# usv_board.net
KiCad netlist of a schematic drawn in EAGLE
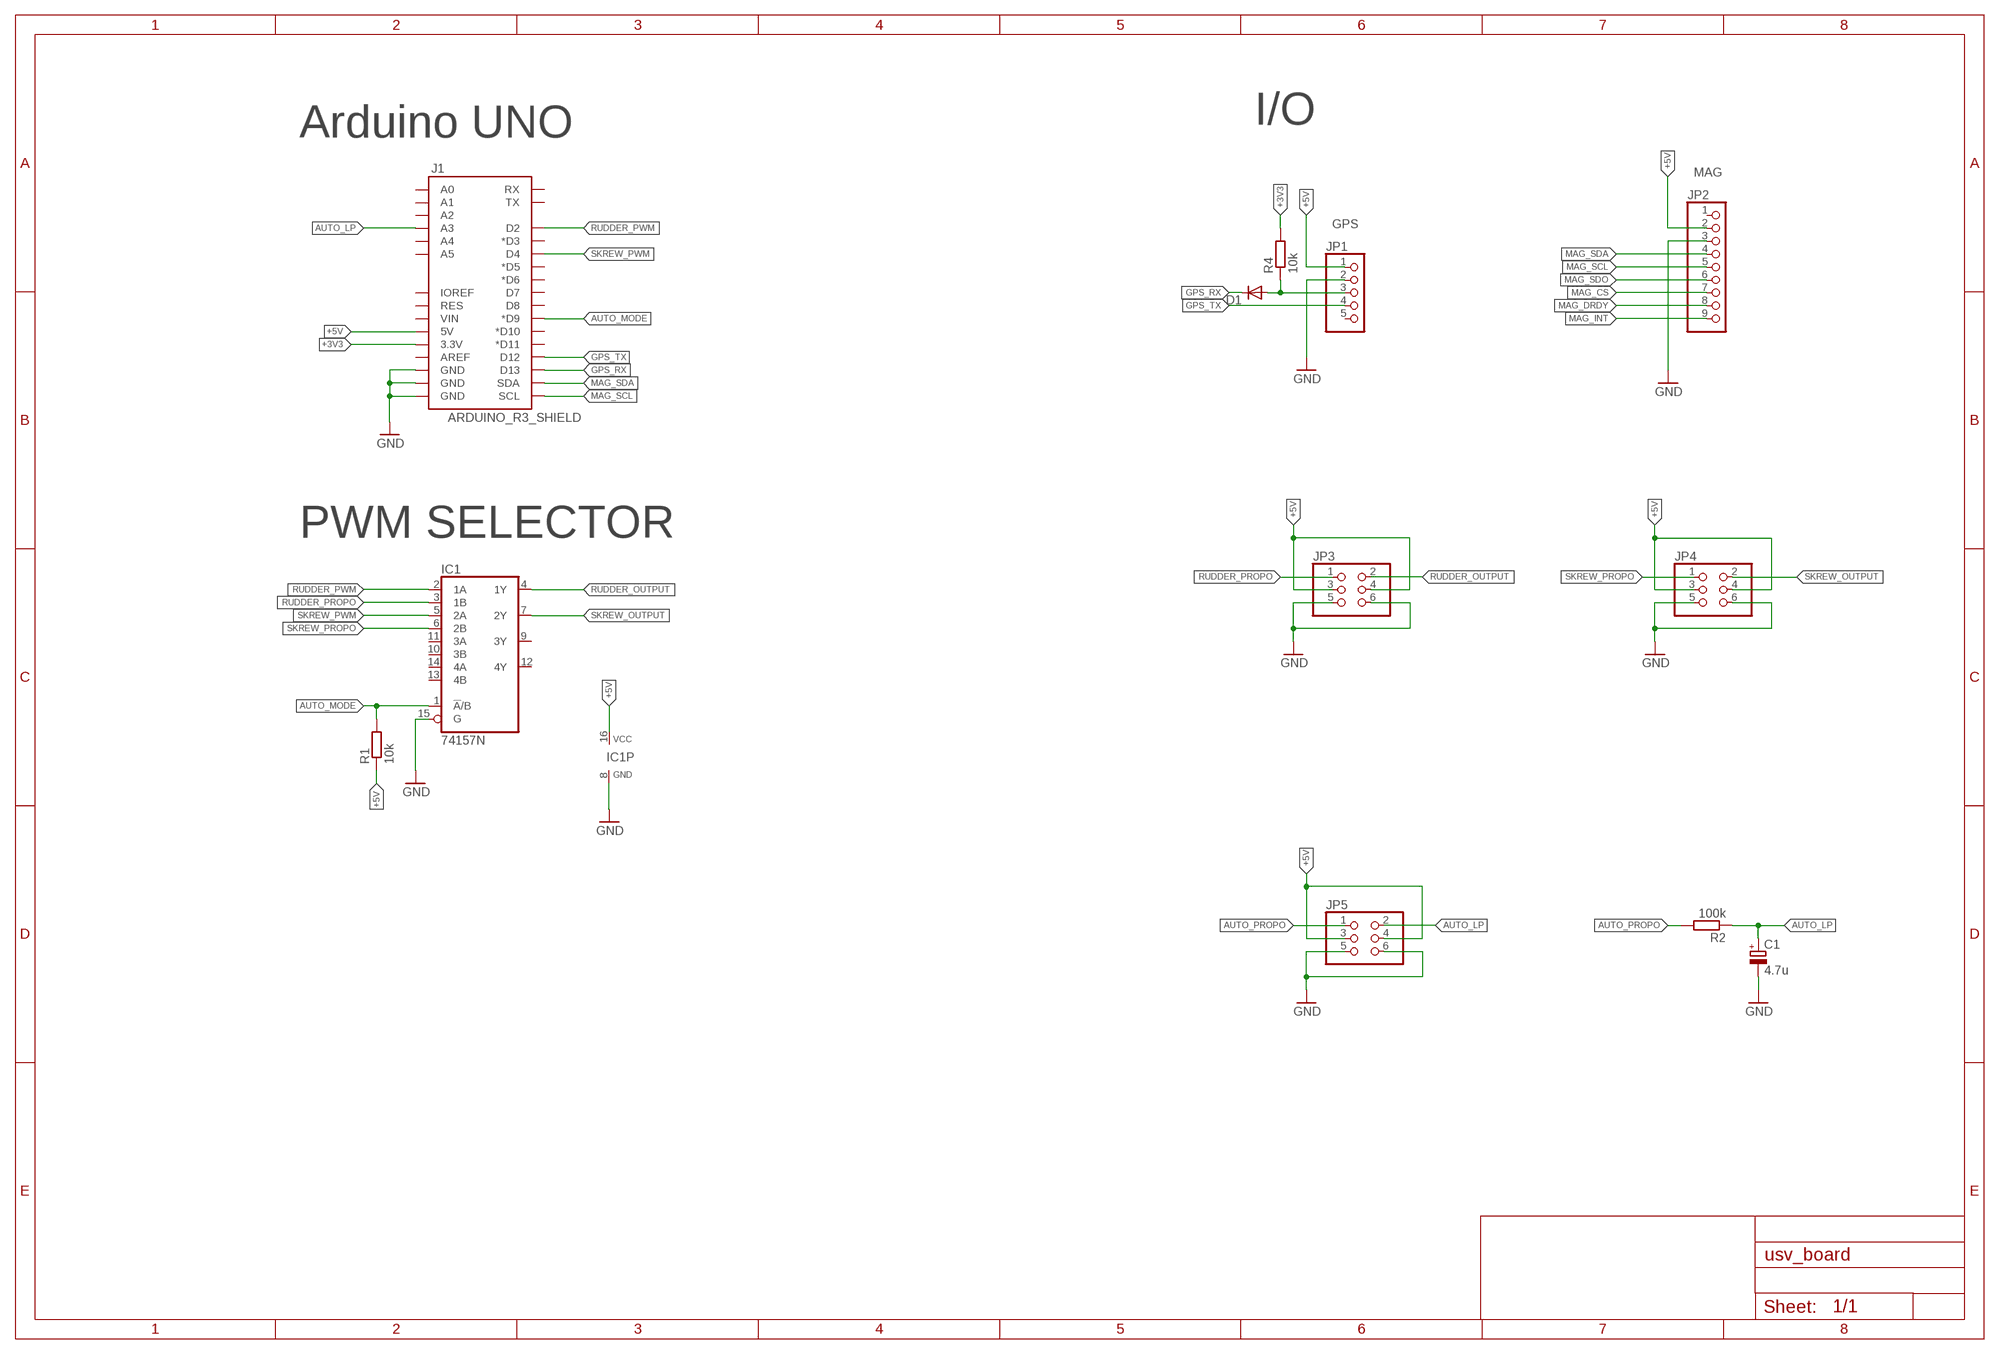
[diagram p0: schematic, sheet 1]

(export (version "E")
  (design (tool "Eeschema 10.0.6"))
  (components
    (comp (ref "C1")
      (value "4.7u")
      (footprint "eagle-import:E2-4")
      (libsource (lib "eagle-import") (part "CPOL-EUE2-4"))
    )
    (comp (ref "D1")
      (value "DIODE-D-7.5")
      (footprint "eagle-import:D-7.5")
      (libsource (lib "eagle-import") (part "DIODE-D-7.5"))
    )
    (comp (ref "IC1")
      (value "74157N")
      (footprint "eagle-import:DIL16")
      (libsource (lib "eagle-import") (part "74157N"))
    )
    (comp (ref "J1")
      (value "ARDUINO_R3_SHIELD")
      (footprint "eagle-import:UNO_R3_SHIELD")
      (libsource (lib "eagle-import") (part "ARDUINO_R3_SHIELD"))
    )
    (comp (ref "JP1")
      (value "PINHD-1X5")
      (footprint "eagle-import:1X05")
      (libsource (lib "eagle-import") (part "PINHD-1X5"))
    )
    (comp (ref "JP2")
      (value "PINHD-1X9")
      (footprint "eagle-import:1X09")
      (libsource (lib "eagle-import") (part "PINHD-1X9"))
    )
    (comp (ref "JP3")
      (value "PINHD-2X3")
      (footprint "eagle-import:2X03")
      (libsource (lib "eagle-import") (part "PINHD-2X3"))
    )
    (comp (ref "JP4")
      (value "PINHD-2X3")
      (footprint "eagle-import:2X03")
      (libsource (lib "eagle-import") (part "PINHD-2X3"))
    )
    (comp (ref "JP5")
      (value "PINHD-2X3")
      (footprint "eagle-import:2X03")
      (libsource (lib "eagle-import") (part "PINHD-2X3"))
    )
    (comp (ref "R1")
      (value "10k")
      (footprint "eagle-import:0207_7")
      (libsource (lib "eagle-import") (part "R-EU_0207/7"))
    )
    (comp (ref "R2")
      (value "100k")
      (footprint "eagle-import:0207_7")
      (libsource (lib "eagle-import") (part "R-EU_0207/7"))
    )
    (comp (ref "R4")
      (value "10k")
      (footprint "eagle-import:0207_7")
      (libsource (lib "eagle-import") (part "R-EU_0207/7"))
    )
  )
  (nets
    (net (code "1") (name "+3V3") (class "Default")
      (node (ref "J1") (pin "3.3V") (pinfunction "3.3V_3.3V") (pintype "bidirectional"))
      (node (ref "R4") (pin "2") (pinfunction "2_2") (pintype "passive"))
    )
    (net (code "2") (name "+5V") (class "Default")
      (node (ref "IC1") (pin "16") (pinfunction "VCC_16") (pintype "power_in"))
      (node (ref "J1") (pin "5V") (pinfunction "5V_5V") (pintype "bidirectional"))
      (node (ref "JP1") (pin "1") (pinfunction "1_1") (pintype "passive"))
      (node (ref "JP2") (pin "2") (pinfunction "2_2") (pintype "passive"))
      (node (ref "JP3") (pin "3") (pinfunction "3_3") (pintype "passive"))
      (node (ref "JP3") (pin "4") (pinfunction "4_4") (pintype "passive"))
      (node (ref "JP4") (pin "3") (pinfunction "3_3") (pintype "passive"))
      (node (ref "JP4") (pin "4") (pinfunction "4_4") (pintype "passive"))
      (node (ref "JP5") (pin "3") (pinfunction "3_3") (pintype "passive"))
      (node (ref "JP5") (pin "4") (pinfunction "4_4") (pintype "passive"))
      (node (ref "R1") (pin "1") (pinfunction "1_1") (pintype "passive"))
    )
    (net (code "3") (name "AUTO_LP") (class "Default")
      (node (ref "C1") (pin "+") (pinfunction "+_+") (pintype "passive"))
      (node (ref "J1") (pin "A3") (pinfunction "A3_A3") (pintype "bidirectional"))
      (node (ref "JP5") (pin "2") (pinfunction "2_2") (pintype "passive"))
      (node (ref "R2") (pin "1") (pinfunction "1_1") (pintype "passive"))
    )
    (net (code "4") (name "AUTO_MODE") (class "Default")
      (node (ref "IC1") (pin "1") (pinfunction "~{A}/B_1") (pintype "input"))
      (node (ref "J1") (pin "D9") (pinfunction "*D9_D9") (pintype "bidirectional"))
      (node (ref "R1") (pin "2") (pinfunction "2_2") (pintype "passive"))
    )
    (net (code "5") (name "AUTO_PROPO") (class "Default")
      (node (ref "JP5") (pin "1") (pinfunction "1_1") (pintype "passive"))
      (node (ref "R2") (pin "2") (pinfunction "2_2") (pintype "passive"))
    )
    (net (code "6") (name "GND") (class "Default")
      (node (ref "C1") (pin "-") (pinfunction "-_-") (pintype "passive"))
      (node (ref "IC1") (pin "15") (pinfunction "G_15") (pintype "input"))
      (node (ref "IC1") (pin "8") (pinfunction "GND_8") (pintype "power_in"))
      (node (ref "J1") (pin "GND@0") (pinfunction "GND_GND@0") (pintype "bidirectional"))
      (node (ref "J1") (pin "GND@1") (pinfunction "GND_GND@1") (pintype "bidirectional"))
      (node (ref "J1") (pin "GND@2") (pinfunction "GND_GND@2") (pintype "bidirectional"))
      (node (ref "JP1") (pin "2") (pinfunction "2_2") (pintype "passive"))
      (node (ref "JP2") (pin "3") (pinfunction "3_3") (pintype "passive"))
      (node (ref "JP3") (pin "5") (pinfunction "5_5") (pintype "passive"))
      (node (ref "JP3") (pin "6") (pinfunction "6_6") (pintype "passive"))
      (node (ref "JP4") (pin "5") (pinfunction "5_5") (pintype "passive"))
      (node (ref "JP4") (pin "6") (pinfunction "6_6") (pintype "passive"))
      (node (ref "JP5") (pin "5") (pinfunction "5_5") (pintype "passive"))
      (node (ref "JP5") (pin "6") (pinfunction "6_6") (pintype "passive"))
    )
    (net (code "7") (name "GPS_RX") (class "Default")
      (node (ref "D1") (pin "C") (pinfunction "C_C") (pintype "passive"))
      (node (ref "J1") (pin "D13") (pinfunction "D13_D13") (pintype "bidirectional"))
    )
    (net (code "8") (name "GPS_TX") (class "Default")
      (node (ref "J1") (pin "D12") (pinfunction "D12_D12") (pintype "bidirectional"))
      (node (ref "JP1") (pin "4") (pinfunction "4_4") (pintype "passive"))
    )
    (net (code "9") (name "MAG_CS") (class "Default")
      (node (ref "JP2") (pin "7") (pinfunction "7_7") (pintype "passive"))
    )
    (net (code "10") (name "MAG_DRDY") (class "Default")
      (node (ref "JP2") (pin "8") (pinfunction "8_8") (pintype "passive"))
    )
    (net (code "11") (name "MAG_INT") (class "Default")
      (node (ref "JP2") (pin "9") (pinfunction "9_9") (pintype "passive"))
    )
    (net (code "12") (name "MAG_SCL") (class "Default")
      (node (ref "J1") (pin "SCL") (pinfunction "SCL_SCL") (pintype "bidirectional"))
      (node (ref "JP2") (pin "5") (pinfunction "5_5") (pintype "passive"))
    )
    (net (code "13") (name "MAG_SDA") (class "Default")
      (node (ref "J1") (pin "SDA") (pinfunction "SDA_SDA") (pintype "bidirectional"))
      (node (ref "JP2") (pin "4") (pinfunction "4_4") (pintype "passive"))
    )
    (net (code "14") (name "MAG_SDO") (class "Default")
      (node (ref "JP2") (pin "6") (pinfunction "6_6") (pintype "passive"))
    )
    (net (code "15") (name "Net-(D1-PadA)") (class "Default")
      (node (ref "D1") (pin "A") (pinfunction "A_A") (pintype "passive"))
      (node (ref "JP1") (pin "3") (pinfunction "3_3") (pintype "passive"))
      (node (ref "R4") (pin "1") (pinfunction "1_1") (pintype "passive"))
    )
    (net (code "16") (name "RUDDER_OUTPUT") (class "Default")
      (node (ref "IC1") (pin "4") (pinfunction "1Y_4") (pintype "output"))
      (node (ref "JP3") (pin "2") (pinfunction "2_2") (pintype "passive"))
    )
    (net (code "17") (name "RUDDER_PROPO") (class "Default")
      (node (ref "IC1") (pin "3") (pinfunction "1B_3") (pintype "input"))
      (node (ref "JP3") (pin "1") (pinfunction "1_1") (pintype "passive"))
    )
    (net (code "18") (name "RUDDER_PWM") (class "Default")
      (node (ref "IC1") (pin "2") (pinfunction "1A_2") (pintype "input"))
      (node (ref "J1") (pin "D2") (pinfunction "D2_D2") (pintype "bidirectional"))
    )
    (net (code "19") (name "SKREW_OUTPUT") (class "Default")
      (node (ref "IC1") (pin "7") (pinfunction "2Y_7") (pintype "output"))
      (node (ref "JP4") (pin "2") (pinfunction "2_2") (pintype "passive"))
    )
    (net (code "20") (name "SKREW_PROPO") (class "Default")
      (node (ref "IC1") (pin "6") (pinfunction "2B_6") (pintype "input"))
      (node (ref "JP4") (pin "1") (pinfunction "1_1") (pintype "passive"))
    )
    (net (code "21") (name "SKREW_PWM") (class "Default")
      (node (ref "IC1") (pin "5") (pinfunction "2A_5") (pintype "input"))
      (node (ref "J1") (pin "D4") (pinfunction "D4_D4") (pintype "bidirectional"))
    )
    (net (code "22") (name "unconnected-(IC1A-3A-Pad11)") (class "Default")
      (node (ref "IC1") (pin "11") (pinfunction "3A_11") (pintype "input"))
    )
    (net (code "23") (name "unconnected-(IC1A-3B-Pad10)") (class "Default")
      (node (ref "IC1") (pin "10") (pinfunction "3B_10") (pintype "input"))
    )
    (net (code "24") (name "unconnected-(IC1A-3Y-Pad9)") (class "Default")
      (node (ref "IC1") (pin "9") (pinfunction "3Y_9") (pintype "output"))
    )
    (net (code "25") (name "unconnected-(IC1A-4A-Pad14)") (class "Default")
      (node (ref "IC1") (pin "14") (pinfunction "4A_14") (pintype "input"))
    )
    (net (code "26") (name "unconnected-(IC1A-4B-Pad13)") (class "Default")
      (node (ref "IC1") (pin "13") (pinfunction "4B_13") (pintype "input"))
    )
    (net (code "27") (name "unconnected-(IC1A-4Y-Pad12)") (class "Default")
      (node (ref "IC1") (pin "12") (pinfunction "4Y_12") (pintype "output"))
    )
    (net (code "28") (name "unconnected-(J1-*D3-PadD3)") (class "Default")
      (node (ref "J1") (pin "D3") (pinfunction "*D3_D3") (pintype "bidirectional"))
    )
    (net (code "29") (name "unconnected-(J1-*D5-PadD5)") (class "Default")
      (node (ref "J1") (pin "D5") (pinfunction "*D5_D5") (pintype "bidirectional"))
    )
    (net (code "30") (name "unconnected-(J1-*D6-PadD6)") (class "Default")
      (node (ref "J1") (pin "D6") (pinfunction "*D6_D6") (pintype "bidirectional"))
    )
    (net (code "31") (name "unconnected-(J1-*D10-PadD10)") (class "Default")
      (node (ref "J1") (pin "D10") (pinfunction "*D10_D10") (pintype "bidirectional"))
    )
    (net (code "32") (name "unconnected-(J1-*D11-PadD11)") (class "Default")
      (node (ref "J1") (pin "D11") (pinfunction "*D11_D11") (pintype "bidirectional"))
    )
    (net (code "33") (name "unconnected-(J1-PadA0)") (class "Default")
      (node (ref "J1") (pin "A0") (pinfunction "A0_A0") (pintype "bidirectional"))
    )
    (net (code "34") (name "unconnected-(J1-PadA1)") (class "Default")
      (node (ref "J1") (pin "A1") (pinfunction "A1_A1") (pintype "bidirectional"))
    )
    (net (code "35") (name "unconnected-(J1-PadA2)") (class "Default")
      (node (ref "J1") (pin "A2") (pinfunction "A2_A2") (pintype "bidirectional"))
    )
    (net (code "36") (name "unconnected-(J1-PadA4)") (class "Default")
      (node (ref "J1") (pin "A4") (pinfunction "A4_A4") (pintype "bidirectional"))
    )
    (net (code "37") (name "unconnected-(J1-PadA5)") (class "Default")
      (node (ref "J1") (pin "A5") (pinfunction "A5_A5") (pintype "bidirectional"))
    )
    (net (code "38") (name "unconnected-(J1-PadAREF)") (class "Default")
      (node (ref "J1") (pin "AREF") (pinfunction "AREF_AREF") (pintype "bidirectional"))
    )
    (net (code "39") (name "unconnected-(J1-PadD7)") (class "Default")
      (node (ref "J1") (pin "D7") (pinfunction "D7_D7") (pintype "bidirectional"))
    )
    (net (code "40") (name "unconnected-(J1-PadD8)") (class "Default")
      (node (ref "J1") (pin "D8") (pinfunction "D8_D8") (pintype "bidirectional"))
    )
    (net (code "41") (name "unconnected-(J1-PadIOREF)") (class "Default")
      (node (ref "J1") (pin "IOREF") (pinfunction "IOREF_IOREF") (pintype "bidirectional"))
    )
    (net (code "42") (name "unconnected-(J1-PadRES)") (class "Default")
      (node (ref "J1") (pin "RES") (pinfunction "RES_RES") (pintype "bidirectional"))
    )
    (net (code "43") (name "unconnected-(J1-PadRX)") (class "Default")
      (node (ref "J1") (pin "RX") (pinfunction "RX_RX") (pintype "bidirectional"))
    )
    (net (code "44") (name "unconnected-(J1-PadTX)") (class "Default")
      (node (ref "J1") (pin "TX") (pinfunction "TX_TX") (pintype "bidirectional"))
    )
    (net (code "45") (name "unconnected-(J1-PadVIN)") (class "Default")
      (node (ref "J1") (pin "VIN") (pinfunction "VIN_VIN") (pintype "bidirectional"))
    )
    (net (code "46") (name "unconnected-(JP1-Pad5)") (class "Default")
      (node (ref "JP1") (pin "5") (pinfunction "5_5") (pintype "passive"))
    )
    (net (code "47") (name "unconnected-(JP2-Pad1)") (class "Default")
      (node (ref "JP2") (pin "1") (pinfunction "1_1") (pintype "passive"))
    )
  )
)
